# Otomasyon_kart.net
KiCad netlist of a schematic drawn in EAGLE
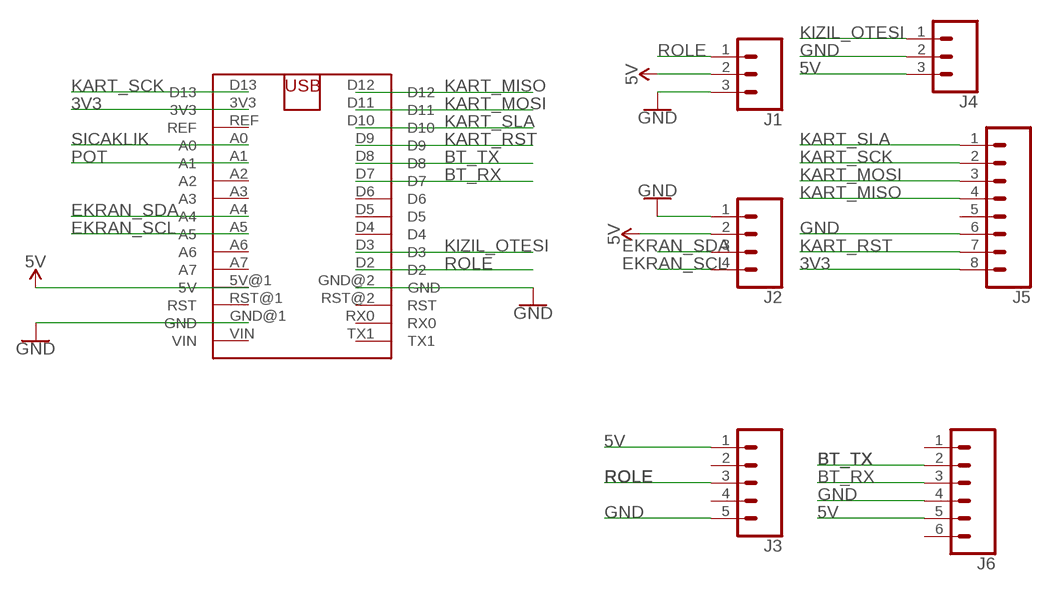
[diagram p0: schematic, sheet 1]

(export (version "E")
  (design (tool "Eeschema 10.0.6"))
  (components
    (comp (ref "J1")
      (value "CONN_03")
      (footprint "eagle-import:1X03")
      (libsource (lib "eagle-import") (part "CONN_03"))
    )
    (comp (ref "J2")
      (value "CONN_04")
      (footprint "eagle-import:1X04")
      (libsource (lib "eagle-import") (part "CONN_04"))
    )
    (comp (ref "J3")
      (value "CONN_05")
      (footprint "eagle-import:1X05")
      (libsource (lib "eagle-import") (part "CONN_05"))
    )
    (comp (ref "J4")
      (value "CONN_03")
      (footprint "eagle-import:1X03")
      (libsource (lib "eagle-import") (part "CONN_03"))
    )
    (comp (ref "J5")
      (value "CONN_08\"")
      (footprint "eagle-import:1X08")
      (libsource (lib "eagle-import") (part "CONN_08{dblquote}"))
    )
    (comp (ref "J6")
      (value "CONN_06LOCK")
      (footprint "eagle-import:1X06_LOCK")
      (libsource (lib "eagle-import") (part "CONN_06LOCK"))
    )
    (comp (ref "U$1")
      (value "ARDUINO_NANO")
      (footprint "eagle-import:ARDUINO_NANO")
      (libsource (lib "eagle-import") (part "ARDUINO_NANO"))
    )
  )
  (nets
    (net (code "1") (name "/3V3") (class "Default")
      (node (ref "J5") (pin "8") (pinfunction "8_8") (pintype "passive"))
      (node (ref "U$1") (pin "3V3") (pinfunction "3V3_3V3") (pintype "bidirectional"))
    )
    (net (code "2") (name "/BT_RX") (class "Default")
      (node (ref "J6") (pin "3") (pinfunction "3_3") (pintype "passive"))
      (node (ref "U$1") (pin "D7") (pinfunction "D7_D7") (pintype "bidirectional"))
    )
    (net (code "3") (name "/BT_TX") (class "Default")
      (node (ref "J6") (pin "2") (pinfunction "2_2") (pintype "passive"))
      (node (ref "U$1") (pin "D8") (pinfunction "D8_D8") (pintype "bidirectional"))
    )
    (net (code "4") (name "/EKRAN_SCL") (class "Default")
      (node (ref "J2") (pin "4") (pinfunction "4_4") (pintype "passive"))
      (node (ref "U$1") (pin "A5") (pinfunction "A5_A5") (pintype "bidirectional"))
    )
    (net (code "5") (name "/EKRAN_SDA") (class "Default")
      (node (ref "J2") (pin "3") (pinfunction "3_3") (pintype "passive"))
      (node (ref "U$1") (pin "A4") (pinfunction "A4_A4") (pintype "bidirectional"))
    )
    (net (code "6") (name "/KART_MISO") (class "Default")
      (node (ref "J5") (pin "4") (pinfunction "4_4") (pintype "passive"))
      (node (ref "U$1") (pin "D12") (pinfunction "D12_D12") (pintype "bidirectional"))
    )
    (net (code "7") (name "/KART_MOSI") (class "Default")
      (node (ref "J5") (pin "3") (pinfunction "3_3") (pintype "passive"))
      (node (ref "U$1") (pin "D11") (pinfunction "D11_D11") (pintype "bidirectional"))
    )
    (net (code "8") (name "/KART_RST") (class "Default")
      (node (ref "J5") (pin "7") (pinfunction "7_7") (pintype "passive"))
      (node (ref "U$1") (pin "D9") (pinfunction "D9_D9") (pintype "bidirectional"))
    )
    (net (code "9") (name "/KART_SCK") (class "Default")
      (node (ref "J5") (pin "2") (pinfunction "2_2") (pintype "passive"))
      (node (ref "U$1") (pin "D13") (pinfunction "D13_D13") (pintype "bidirectional"))
    )
    (net (code "10") (name "/KART_SLA") (class "Default")
      (node (ref "J5") (pin "1") (pinfunction "1_1") (pintype "passive"))
      (node (ref "U$1") (pin "D10") (pinfunction "D10_D10") (pintype "bidirectional"))
    )
    (net (code "11") (name "/KIZIL_OTESI") (class "Default")
      (node (ref "J4") (pin "1") (pinfunction "1_1") (pintype "passive"))
      (node (ref "U$1") (pin "D3") (pinfunction "D3_D3") (pintype "bidirectional"))
    )
    (net (code "12") (name "/POT") (class "Default")
      (node (ref "U$1") (pin "A1") (pinfunction "A1_A1") (pintype "bidirectional"))
    )
    (net (code "13") (name "/ROLE") (class "Default")
      (node (ref "J1") (pin "1") (pinfunction "1_1") (pintype "passive"))
      (node (ref "J3") (pin "3") (pinfunction "3_3") (pintype "passive"))
      (node (ref "U$1") (pin "D2") (pinfunction "D2_D2") (pintype "bidirectional"))
    )
    (net (code "14") (name "/SICAKLIK") (class "Default")
      (node (ref "U$1") (pin "A0") (pinfunction "A0_A0") (pintype "bidirectional"))
    )
    (net (code "15") (name "5V") (class "Default")
      (node (ref "J1") (pin "2") (pinfunction "2_2") (pintype "passive"))
      (node (ref "J2") (pin "2") (pinfunction "2_2") (pintype "passive"))
      (node (ref "J3") (pin "1") (pinfunction "1_1") (pintype "passive"))
      (node (ref "J4") (pin "3") (pinfunction "3_3") (pintype "passive"))
      (node (ref "J6") (pin "5") (pinfunction "5_5") (pintype "passive"))
      (node (ref "U$1") (pin "5V@1") (pinfunction "5V_5V@1") (pintype "bidirectional"))
    )
    (net (code "16") (name "GND") (class "Default")
      (node (ref "J1") (pin "3") (pinfunction "3_3") (pintype "passive"))
      (node (ref "J2") (pin "1") (pinfunction "1_1") (pintype "passive"))
      (node (ref "J3") (pin "5") (pinfunction "5_5") (pintype "passive"))
      (node (ref "J4") (pin "2") (pinfunction "2_2") (pintype "passive"))
      (node (ref "J5") (pin "6") (pinfunction "6_6") (pintype "passive"))
      (node (ref "J6") (pin "4") (pinfunction "4_4") (pintype "passive"))
      (node (ref "U$1") (pin "GND@1") (pinfunction "GND_GND@1") (pintype "bidirectional"))
      (node (ref "U$1") (pin "GND@2") (pinfunction "GND_GND@2") (pintype "bidirectional"))
    )
    (net (code "17") (name "unconnected-(J3-Pad2)") (class "Default")
      (node (ref "J3") (pin "2") (pinfunction "2_2") (pintype "passive"))
    )
    (net (code "18") (name "unconnected-(J3-Pad4)") (class "Default")
      (node (ref "J3") (pin "4") (pinfunction "4_4") (pintype "passive"))
    )
    (net (code "19") (name "unconnected-(J5-Pad5)") (class "Default")
      (node (ref "J5") (pin "5") (pinfunction "5_5") (pintype "passive"))
    )
    (net (code "20") (name "unconnected-(J6-Pad1)") (class "Default")
      (node (ref "J6") (pin "1") (pinfunction "1_1") (pintype "passive"))
    )
    (net (code "21") (name "unconnected-(J6-Pad6)") (class "Default")
      (node (ref "J6") (pin "6") (pinfunction "6_6") (pintype "passive"))
    )
    (net (code "22") (name "unconnected-(U$1-PadA2)") (class "Default")
      (node (ref "U$1") (pin "A2") (pinfunction "A2_A2") (pintype "bidirectional"))
    )
    (net (code "23") (name "unconnected-(U$1-PadA3)") (class "Default")
      (node (ref "U$1") (pin "A3") (pinfunction "A3_A3") (pintype "bidirectional"))
    )
    (net (code "24") (name "unconnected-(U$1-PadA6)") (class "Default")
      (node (ref "U$1") (pin "A6") (pinfunction "A6_A6") (pintype "bidirectional"))
    )
    (net (code "25") (name "unconnected-(U$1-PadA7)") (class "Default")
      (node (ref "U$1") (pin "A7") (pinfunction "A7_A7") (pintype "bidirectional"))
    )
    (net (code "26") (name "unconnected-(U$1-PadD4)") (class "Default")
      (node (ref "U$1") (pin "D4") (pinfunction "D4_D4") (pintype "bidirectional"))
    )
    (net (code "27") (name "unconnected-(U$1-PadD5)") (class "Default")
      (node (ref "U$1") (pin "D5") (pinfunction "D5_D5") (pintype "bidirectional"))
    )
    (net (code "28") (name "unconnected-(U$1-PadD6)") (class "Default")
      (node (ref "U$1") (pin "D6") (pinfunction "D6_D6") (pintype "bidirectional"))
    )
    (net (code "29") (name "unconnected-(U$1-PadREF)") (class "Default")
      (node (ref "U$1") (pin "REF") (pinfunction "REF_REF") (pintype "bidirectional"))
    )
    (net (code "30") (name "unconnected-(U$1-PadRX0)") (class "Default")
      (node (ref "U$1") (pin "RX0") (pinfunction "RX0_RX0") (pintype "bidirectional"))
    )
    (net (code "31") (name "unconnected-(U$1-PadTX1)") (class "Default")
      (node (ref "U$1") (pin "TX1") (pinfunction "TX1_TX1") (pintype "bidirectional"))
    )
    (net (code "32") (name "unconnected-(U$1-PadVIN)") (class "Default")
      (node (ref "U$1") (pin "VIN") (pinfunction "VIN_VIN") (pintype "bidirectional"))
    )
    (net (code "33") (name "unconnected-(U$1-RST-PadRST@1)") (class "Default")
      (node (ref "U$1") (pin "RST@1") (pinfunction "RST_RST@1") (pintype "bidirectional"))
    )
    (net (code "34") (name "unconnected-(U$1-RST-PadRST@2)") (class "Default")
      (node (ref "U$1") (pin "RST@2") (pinfunction "RST_RST@2") (pintype "bidirectional"))
    )
  )
)
